# Gadget-Box-atmega32u4.net
KiCad netlist of a schematic drawn in EAGLE
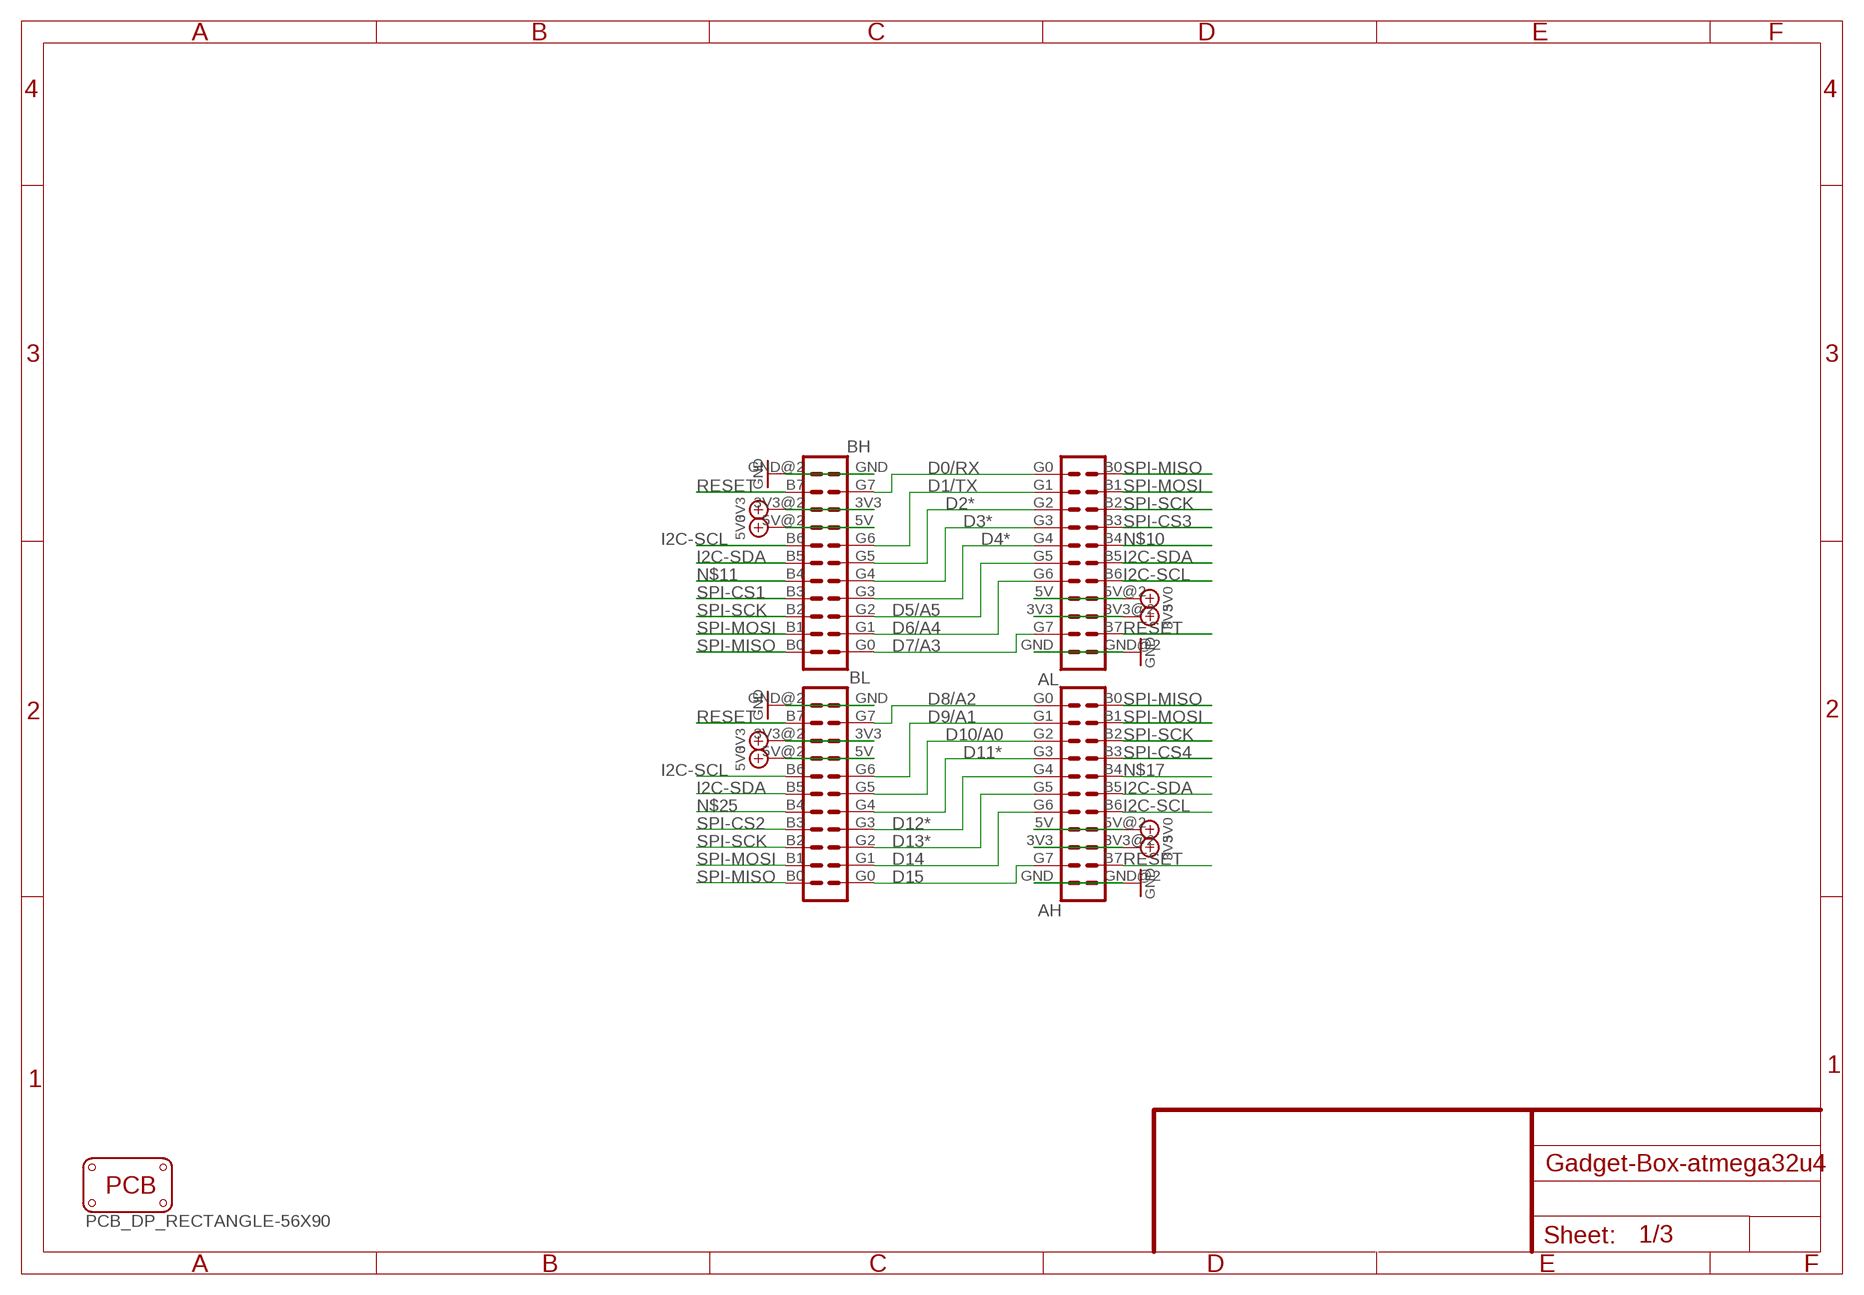
[diagram p0: schematic, sheet 1]
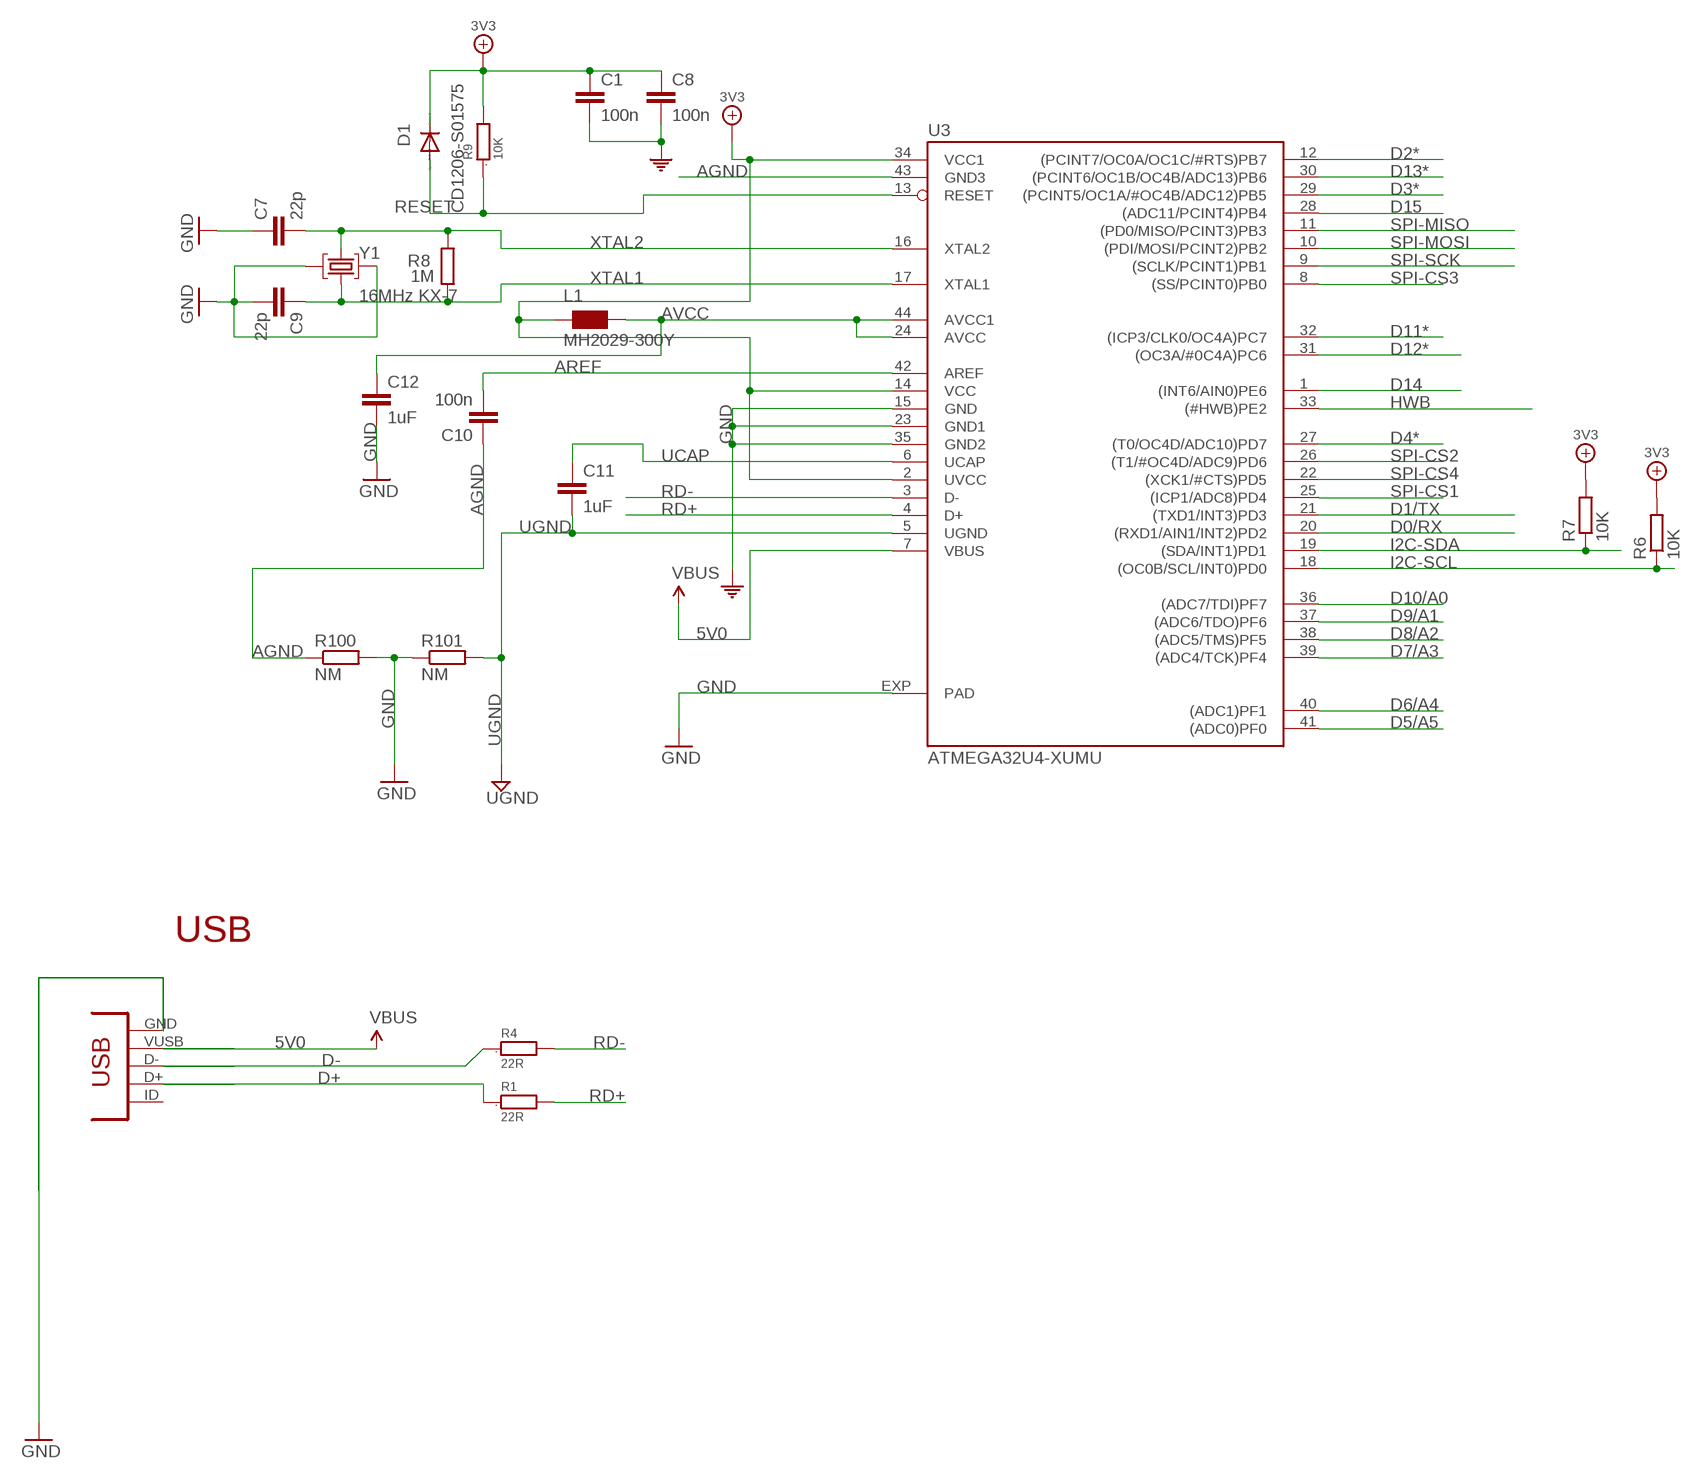
[diagram p1: schematic, sheet 2, part 1 of 2]
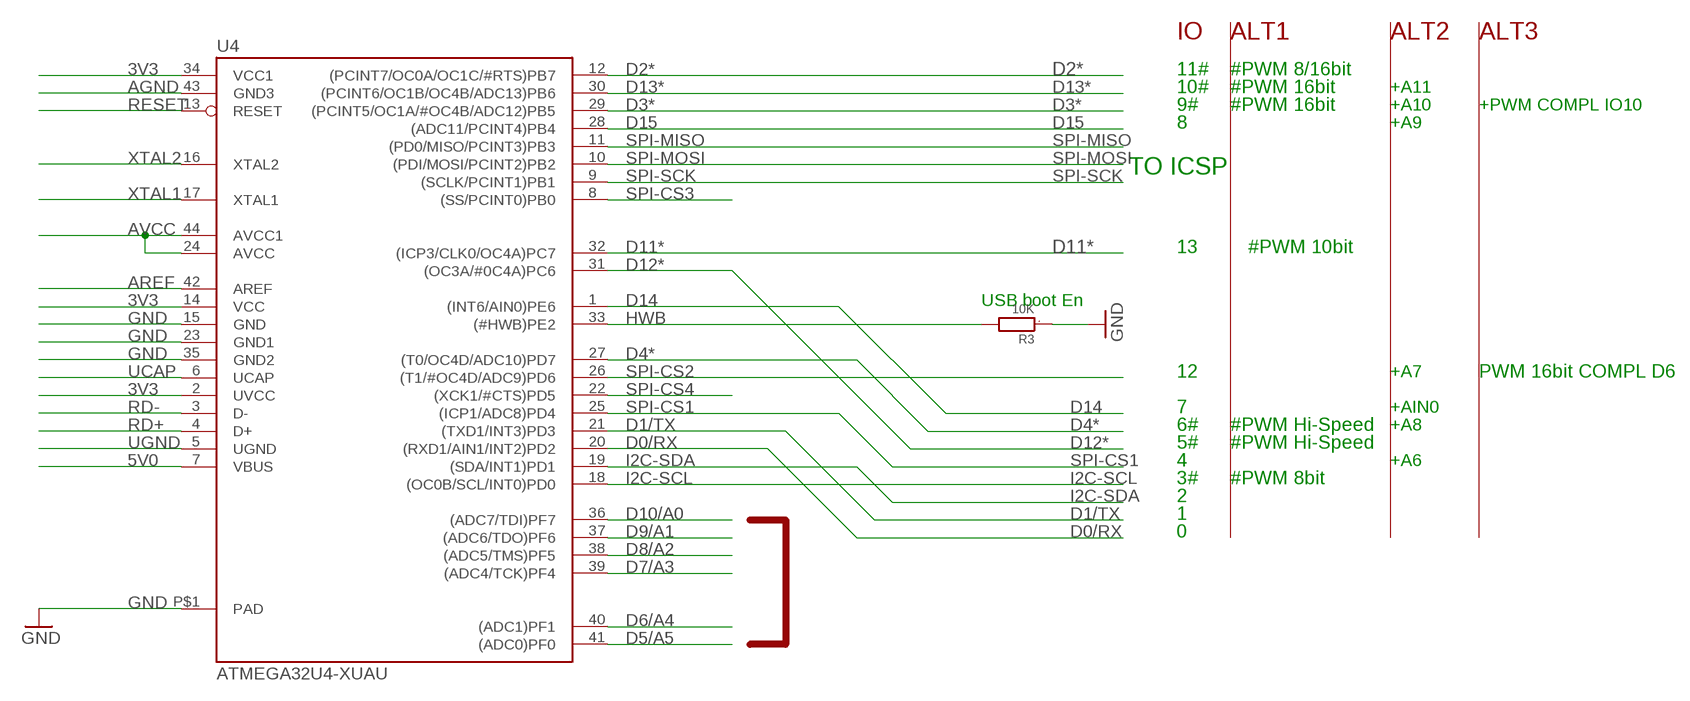
[diagram p2: schematic, sheet 2, part 2 of 2]
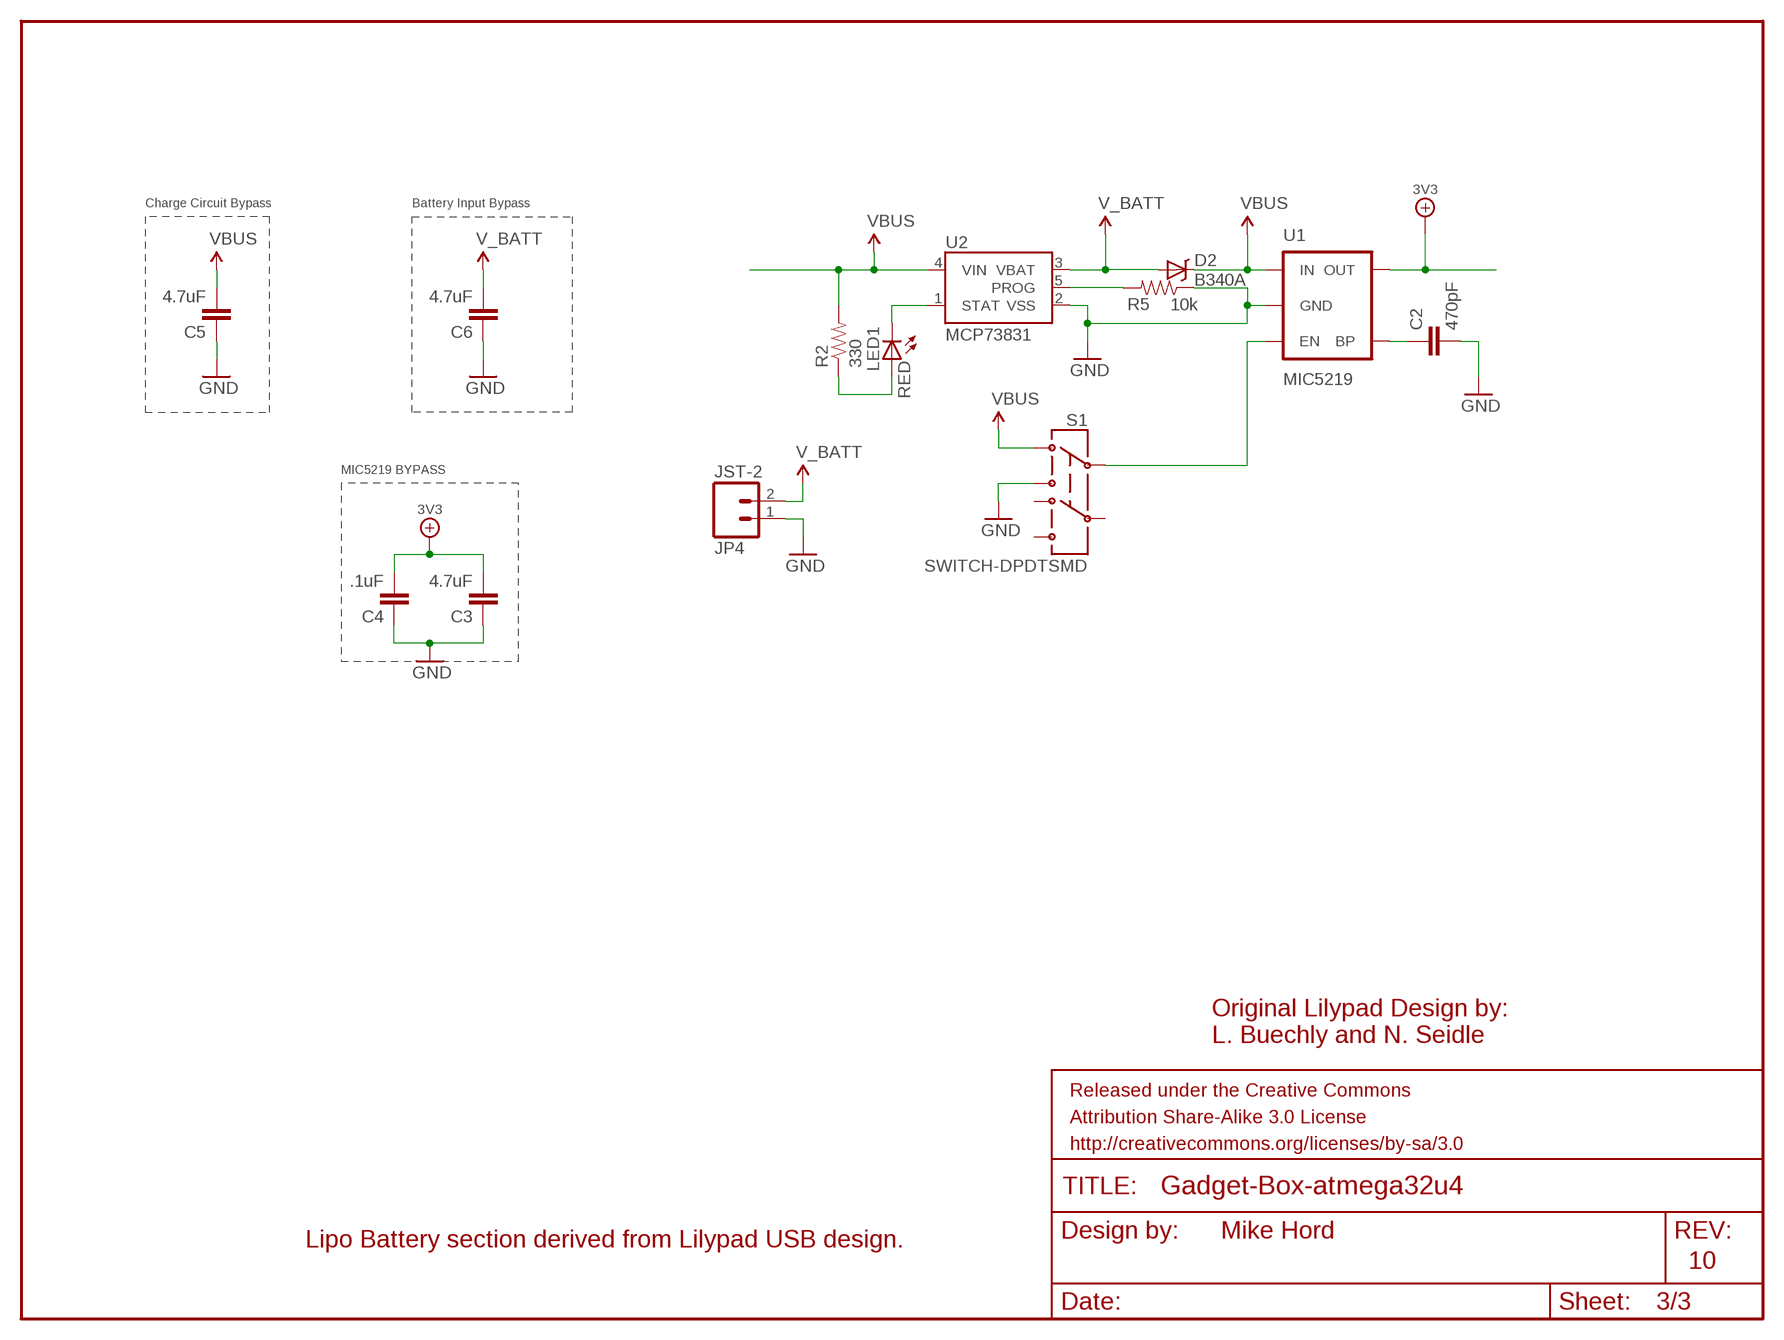
[diagram p3: schematic, sheet 3]

(export (version "E")
  (design (tool "Eeschema 10.0.6"))
  (components
    (comp (ref "C1")
      (value "100n")
      (footprint "eagle-import:C0603-ROUND")
      (libsource (lib "eagle-import") (part "C-EUC0603"))
    )
    (comp (ref "C7")
      (value "22p")
      (footprint "eagle-import:C0603-ROUND")
      (libsource (lib "eagle-import") (part "C-EUC0603"))
    )
    (comp (ref "C8")
      (value "100n")
      (footprint "eagle-import:C0603-ROUND")
      (libsource (lib "eagle-import") (part "C-EUC0603"))
    )
    (comp (ref "C9")
      (value "22p")
      (footprint "eagle-import:C0603-ROUND")
      (libsource (lib "eagle-import") (part "C-EUC0603"))
    )
    (comp (ref "C10")
      (value "100n")
      (footprint "eagle-import:C0603-ROUND")
      (libsource (lib "eagle-import") (part "C-EUC0603"))
    )
    (comp (ref "C11")
      (value "1uF")
      (footprint "eagle-import:C0603-ROUND")
      (libsource (lib "eagle-import") (part "C-EUC0603"))
    )
    (comp (ref "C12")
      (value "1uF")
      (footprint "eagle-import:C0603-ROUND")
      (libsource (lib "eagle-import") (part "C-EUC0603"))
    )
    (comp (ref "D1")
      (value "CD1206-S01575")
      (footprint "eagle-import:MINIMELF")
      (libsource (lib "eagle-import") (part "DIODE-MINIMELF"))
    )
    (comp (ref "L1")
      (value "MH2029-300Y")
      (footprint "eagle-import:0805")
      (libsource (lib "eagle-import") (part "WE-CBF_0805"))
    )
    (comp (ref "R1")
      (value "22R")
      (footprint "eagle-import:0805")
      (libsource (lib "eagle-import") (part "R0805"))
    )
    (comp (ref "R3")
      (value "10K")
      (footprint "eagle-import:0805")
      (libsource (lib "eagle-import") (part "R0805"))
    )
    (comp (ref "R4")
      (value "22R")
      (footprint "eagle-import:0805")
      (libsource (lib "eagle-import") (part "R0805"))
    )
    (comp (ref "R6")
      (value "10K")
      (footprint "eagle-import:R0402")
      (libsource (lib "eagle-import") (part "R-EU_R0402"))
    )
    (comp (ref "R7")
      (value "10K")
      (footprint "eagle-import:R0402")
      (libsource (lib "eagle-import") (part "R-EU_R0402"))
    )
    (comp (ref "R8")
      (value "1M")
      (footprint "eagle-import:R0603-ROUND")
      (libsource (lib "eagle-import") (part "R-EU_R0603"))
    )
    (comp (ref "R9")
      (value "10K")
      (footprint "eagle-import:0805")
      (libsource (lib "eagle-import") (part "R0805"))
    )
    (comp (ref "R100")
      (value "NM")
      (footprint "eagle-import:R0402")
      (libsource (lib "eagle-import") (part "R-EU_R0402"))
    )
    (comp (ref "R101")
      (value "NM")
      (footprint "eagle-import:R0402")
      (libsource (lib "eagle-import") (part "R-EU_R0402"))
    )
    (comp (ref "U3")
      (value "ATMEGA32U4-XUMU")
      (footprint "eagle-import:QFN44ML7X7")
      (libsource (lib "eagle-import") (part "ATMEGA32U4-XUMU"))
    )
    (comp (ref "U4")
      (value "ATMEGA32U4-XUAU")
      (footprint "eagle-import:TQFP44-PAD")
      (libsource (lib "eagle-import") (part "ATMEGA32U4-XUAU"))
    )
    (comp (ref "USB")
      (value "CONN_USB")
      (footprint "eagle-import:CONN_USB_MINI-B")
      (libsource (lib "eagle-import") (part "CONN_USB"))
    )
    (comp (ref "Y1")
      (value "16MHz KX-7")
      (footprint "eagle-import:CRYSTAL-3.2-2.5")
      (libsource (lib "eagle-import") (part "CRYSTAL-3.2-2.5"))
    )
    (comp (ref "AH")
      (value "ECOGECOG_SLOT")
      (footprint "eagle-import:ECOG")
      (libsource (lib "eagle-import") (part "ECOGECOG_SLOT"))
    )
    (comp (ref "AL")
      (value "ECOGECOG_SLOT")
      (footprint "eagle-import:ECOG")
      (libsource (lib "eagle-import") (part "ECOGECOG_SLOT"))
    )
    (comp (ref "BH")
      (value "ECOGECOG_SLOT")
      (footprint "eagle-import:ECOG")
      (libsource (lib "eagle-import") (part "ECOGECOG_SLOT"))
    )
    (comp (ref "BL")
      (value "ECOGECOG_SLOT")
      (footprint "eagle-import:ECOG")
      (libsource (lib "eagle-import") (part "ECOGECOG_SLOT"))
    )
    (comp (ref "PCB1")
      (value "PCB_DP_RECTANGLE-56X90")
      (footprint "eagle-import:DP9056_V1")
      (libsource (lib "eagle-import") (part "PCB_DP_RECTANGLE-56X90"))
    )
    (comp (ref "C2")
      (value "470pF")
      (footprint "eagle-import:0603-CAP")
      (libsource (lib "eagle-import") (part "CAP0603-CAP"))
    )
    (comp (ref "C3")
      (value "4.7uF")
      (footprint "eagle-import:0603-CAP")
      (libsource (lib "eagle-import") (part "CAP0603-CAP"))
    )
    (comp (ref "C4")
      (value ".1uF")
      (footprint "eagle-import:0603-CAP")
      (libsource (lib "eagle-import") (part "CAP0603-CAP"))
    )
    (comp (ref "C5")
      (value "4.7uF")
      (footprint "eagle-import:1206")
      (libsource (lib "eagle-import") (part "CAP1206"))
    )
    (comp (ref "C6")
      (value "4.7uF")
      (footprint "eagle-import:1206")
      (libsource (lib "eagle-import") (part "CAP1206"))
    )
    (comp (ref "D2")
      (value "B340A")
      (footprint "eagle-import:SMA-DIODE")
      (libsource (lib "eagle-import") (part "DIODE-SCHOTTKY_"))
    )
    (comp (ref "JP4")
      (value "JST-2")
      (footprint "eagle-import:JST-2-SMD")
      (libsource (lib "eagle-import") (part "M02-JST-2MM-SMT"))
    )
    (comp (ref "LED1")
      (value "RED")
      (footprint "eagle-import:LED-0603")
      (libsource (lib "eagle-import") (part "LED0603"))
    )
    (comp (ref "R2")
      (value "330")
      (footprint "eagle-import:0603-RES")
      (libsource (lib "eagle-import") (part "RESISTOR0603-RES"))
    )
    (comp (ref "R5")
      (value "10k")
      (footprint "eagle-import:0603-RES")
      (libsource (lib "eagle-import") (part "RESISTOR0603-RES"))
    )
    (comp (ref "S1")
      (value "SWITCH-DPDTSMD")
      (footprint "eagle-import:AYZ0202")
      (libsource (lib "eagle-import") (part "SWITCH-DPDTSMD"))
    )
    (comp (ref "U1")
      (value "MIC5219")
      (footprint "eagle-import:SOT23-5")
      (libsource (lib "eagle-import") (part "V_REG_MIC5219SMD"))
    )
    (comp (ref "U2")
      (value "MCP73831")
      (footprint "eagle-import:SOT23-5")
      (libsource (lib "eagle-import") (part "MCP73831"))
    )
  )
  (nets
    (net (code "1") (name "3V3") (class "Default")
      (node (ref "AH") (pin "3V3") (pinfunction "3V3_3V3") (pintype "passive"))
      (node (ref "AH") (pin "3V3@2") (pinfunction "3V3_3V3@2") (pintype "passive"))
      (node (ref "AL") (pin "3V3") (pinfunction "3V3_3V3") (pintype "passive"))
      (node (ref "AL") (pin "3V3@2") (pinfunction "3V3_3V3@2") (pintype "passive"))
      (node (ref "BH") (pin "3V3") (pinfunction "3V3_3V3") (pintype "passive"))
      (node (ref "BH") (pin "3V3@2") (pinfunction "3V3_3V3@2") (pintype "passive"))
      (node (ref "BL") (pin "3V3") (pinfunction "3V3_3V3") (pintype "passive"))
      (node (ref "BL") (pin "3V3@2") (pinfunction "3V3_3V3@2") (pintype "passive"))
      (node (ref "C1") (pin "1") (pinfunction "1_1") (pintype "passive"))
      (node (ref "C3") (pin "2") (pinfunction "2_2") (pintype "passive"))
      (node (ref "C4") (pin "2") (pinfunction "2_2") (pintype "passive"))
      (node (ref "C8") (pin "1") (pinfunction "1_1") (pintype "passive"))
      (node (ref "D1") (pin "C") (pinfunction "C_C") (pintype "passive"))
      (node (ref "L1") (pin "1") (pinfunction "1_1") (pintype "passive"))
      (node (ref "R6") (pin "2") (pinfunction "2_2") (pintype "passive"))
      (node (ref "R7") (pin "2") (pinfunction "2_2") (pintype "passive"))
      (node (ref "R9") (pin "2") (pinfunction "2_2") (pintype "passive"))
      (node (ref "U1") (pin "5") (pinfunction "OUT_5") (pintype "passive"))
      (node (ref "U3") (pin "14") (pinfunction "VCC_14") (pintype "power_in"))
      (node (ref "U3") (pin "2") (pinfunction "UVCC_2") (pintype "power_in"))
      (node (ref "U3") (pin "34") (pinfunction "VCC1_34") (pintype "power_in"))
      (node (ref "U4") (pin "14") (pinfunction "VCC_14") (pintype "power_in"))
      (node (ref "U4") (pin "2") (pinfunction "UVCC_2") (pintype "power_in"))
      (node (ref "U4") (pin "34") (pinfunction "VCC1_34") (pintype "power_in"))
    )
    (net (code "2") (name "5V0") (class "Default")
      (node (ref "AH") (pin "5V") (pinfunction "5V_5V") (pintype "passive"))
      (node (ref "AH") (pin "5V@2") (pinfunction "5V_5V@2") (pintype "passive"))
      (node (ref "AL") (pin "5V") (pinfunction "5V_5V") (pintype "passive"))
      (node (ref "AL") (pin "5V@2") (pinfunction "5V_5V@2") (pintype "passive"))
      (node (ref "BH") (pin "5V") (pinfunction "5V_5V") (pintype "passive"))
      (node (ref "BH") (pin "5V@2") (pinfunction "5V_5V@2") (pintype "passive"))
      (node (ref "BL") (pin "5V") (pinfunction "5V_5V") (pintype "passive"))
      (node (ref "BL") (pin "5V@2") (pinfunction "5V_5V@2") (pintype "passive"))
      (node (ref "C5") (pin "2") (pinfunction "2_2") (pintype "passive"))
      (node (ref "D2") (pin "C") (pinfunction "C_C") (pintype "passive"))
      (node (ref "R2") (pin "2") (pinfunction "2_2") (pintype "passive"))
      (node (ref "S1") (pin "1") (pinfunction "1_1") (pintype "bidirectional"))
      (node (ref "U1") (pin "1") (pinfunction "IN_1") (pintype "input"))
      (node (ref "U2") (pin "4") (pinfunction "VIN_4") (pintype "power_in"))
      (node (ref "U3") (pin "7") (pinfunction "VBUS_7") (pintype "input"))
      (node (ref "U4") (pin "7") (pinfunction "VBUS_7") (pintype "input"))
      (node (ref "USB") (pin "VUSB") (pinfunction "VUSB_VUSB") (pintype "bidirectional"))
    )
    (net (code "3") (name "AGND") (class "Default")
      (node (ref "C10") (pin "1") (pinfunction "1_1") (pintype "passive"))
      (node (ref "R100") (pin "1") (pinfunction "1_1") (pintype "passive"))
      (node (ref "U3") (pin "43") (pinfunction "GND3_43") (pintype "power_in"))
      (node (ref "U4") (pin "43") (pinfunction "GND3_43") (pintype "power_in"))
    )
    (net (code "4") (name "AREF") (class "Default")
      (node (ref "C10") (pin "2") (pinfunction "2_2") (pintype "passive"))
      (node (ref "U3") (pin "42") (pinfunction "AREF_42") (pintype "power_in"))
      (node (ref "U4") (pin "42") (pinfunction "AREF_42") (pintype "power_in"))
    )
    (net (code "5") (name "AVCC") (class "Default")
      (node (ref "C12") (pin "1") (pinfunction "1_1") (pintype "passive"))
      (node (ref "L1") (pin "2") (pinfunction "2_2") (pintype "passive"))
      (node (ref "U3") (pin "24") (pinfunction "AVCC_24") (pintype "power_in"))
      (node (ref "U3") (pin "44") (pinfunction "AVCC1_44") (pintype "power_in"))
      (node (ref "U4") (pin "24") (pinfunction "AVCC_24") (pintype "power_in"))
      (node (ref "U4") (pin "44") (pinfunction "AVCC1_44") (pintype "power_in"))
    )
    (net (code "6") (name "D+") (class "Default")
      (node (ref "R1") (pin "1") (pinfunction "1_1") (pintype "passive"))
      (node (ref "USB") (pin "D+") (pinfunction "D+_D+") (pintype "bidirectional"))
    )
    (net (code "7") (name "D-") (class "Default")
      (node (ref "R4") (pin "1") (pinfunction "1_1") (pintype "passive"))
      (node (ref "USB") (pin "D-") (pinfunction "D-_D-") (pintype "bidirectional"))
    )
    (net (code "8") (name "D0{slash}RX") (class "Default")
      (node (ref "AL") (pin "G0") (pinfunction "G0_G0") (pintype "passive"))
      (node (ref "BH") (pin "G7") (pinfunction "G7_G7") (pintype "passive"))
      (node (ref "U3") (pin "20") (pinfunction "(RXD1/AIN1/INT2)PD2_20") (pintype "bidirectional"))
      (node (ref "U4") (pin "20") (pinfunction "(RXD1/AIN1/INT2)PD2_20") (pintype "bidirectional"))
    )
    (net (code "9") (name "D1{slash}TX") (class "Default")
      (node (ref "AL") (pin "G1") (pinfunction "G1_G1") (pintype "passive"))
      (node (ref "BH") (pin "G6") (pinfunction "G6_G6") (pintype "passive"))
      (node (ref "U3") (pin "21") (pinfunction "(TXD1/INT3)PD3_21") (pintype "bidirectional"))
      (node (ref "U4") (pin "21") (pinfunction "(TXD1/INT3)PD3_21") (pintype "bidirectional"))
    )
    (net (code "10") (name "D2*") (class "Default")
      (node (ref "AL") (pin "G2") (pinfunction "G2_G2") (pintype "passive"))
      (node (ref "BH") (pin "G5") (pinfunction "G5_G5") (pintype "passive"))
      (node (ref "U3") (pin "12") (pinfunction "(PCINT7/OC0A/OC1C/#RTS)PB7_12") (pintype "bidirectional"))
      (node (ref "U4") (pin "12") (pinfunction "(PCINT7/OC0A/OC1C/#RTS)PB7_12") (pintype "bidirectional"))
    )
    (net (code "11") (name "D3*") (class "Default")
      (node (ref "AL") (pin "G3") (pinfunction "G3_G3") (pintype "passive"))
      (node (ref "BH") (pin "G4") (pinfunction "G4_G4") (pintype "passive"))
      (node (ref "U3") (pin "29") (pinfunction "(PCINT5/OC1A/#OC4B/ADC12)PB5_29") (pintype "bidirectional"))
      (node (ref "U4") (pin "29") (pinfunction "(PCINT5/OC1A/#OC4B/ADC12)PB5_29") (pintype "bidirectional"))
    )
    (net (code "12") (name "D4*") (class "Default")
      (node (ref "AL") (pin "G4") (pinfunction "G4_G4") (pintype "passive"))
      (node (ref "BH") (pin "G3") (pinfunction "G3_G3") (pintype "passive"))
      (node (ref "U3") (pin "27") (pinfunction "(T0/OC4D/ADC10)PD7_27") (pintype "bidirectional"))
      (node (ref "U4") (pin "27") (pinfunction "(T0/OC4D/ADC10)PD7_27") (pintype "bidirectional"))
    )
    (net (code "13") (name "D5{slash}A5") (class "Default")
      (node (ref "AL") (pin "G5") (pinfunction "G5_G5") (pintype "passive"))
      (node (ref "BH") (pin "G2") (pinfunction "G2_G2") (pintype "passive"))
      (node (ref "U3") (pin "41") (pinfunction "(ADC0)PF0_41") (pintype "bidirectional"))
      (node (ref "U4") (pin "41") (pinfunction "(ADC0)PF0_41") (pintype "bidirectional"))
    )
    (net (code "14") (name "D6{slash}A4") (class "Default")
      (node (ref "AL") (pin "G6") (pinfunction "G6_G6") (pintype "passive"))
      (node (ref "BH") (pin "G1") (pinfunction "G1_G1") (pintype "passive"))
      (node (ref "U3") (pin "40") (pinfunction "(ADC1)PF1_40") (pintype "bidirectional"))
      (node (ref "U4") (pin "40") (pinfunction "(ADC1)PF1_40") (pintype "bidirectional"))
    )
    (net (code "15") (name "D7{slash}A3") (class "Default")
      (node (ref "AL") (pin "G7") (pinfunction "G7_G7") (pintype "passive"))
      (node (ref "BH") (pin "G0") (pinfunction "G0_G0") (pintype "passive"))
      (node (ref "U3") (pin "39") (pinfunction "(ADC4/TCK)PF4_39") (pintype "bidirectional"))
      (node (ref "U4") (pin "39") (pinfunction "(ADC4/TCK)PF4_39") (pintype "bidirectional"))
    )
    (net (code "16") (name "D8{slash}A2") (class "Default")
      (node (ref "AH") (pin "G0") (pinfunction "G0_G0") (pintype "passive"))
      (node (ref "BL") (pin "G7") (pinfunction "G7_G7") (pintype "passive"))
      (node (ref "U3") (pin "38") (pinfunction "(ADC5/TMS)PF5_38") (pintype "bidirectional"))
      (node (ref "U4") (pin "38") (pinfunction "(ADC5/TMS)PF5_38") (pintype "bidirectional"))
    )
    (net (code "17") (name "D9{slash}A1") (class "Default")
      (node (ref "AH") (pin "G1") (pinfunction "G1_G1") (pintype "passive"))
      (node (ref "BL") (pin "G6") (pinfunction "G6_G6") (pintype "passive"))
      (node (ref "U3") (pin "37") (pinfunction "(ADC6/TDO)PF6_37") (pintype "bidirectional"))
      (node (ref "U4") (pin "37") (pinfunction "(ADC6/TDO)PF6_37") (pintype "bidirectional"))
    )
    (net (code "18") (name "D10{slash}A0") (class "Default")
      (node (ref "AH") (pin "G2") (pinfunction "G2_G2") (pintype "passive"))
      (node (ref "BL") (pin "G5") (pinfunction "G5_G5") (pintype "passive"))
      (node (ref "U3") (pin "36") (pinfunction "(ADC7/TDI)PF7_36") (pintype "bidirectional"))
      (node (ref "U4") (pin "36") (pinfunction "(ADC7/TDI)PF7_36") (pintype "bidirectional"))
    )
    (net (code "19") (name "D11*") (class "Default")
      (node (ref "AH") (pin "G3") (pinfunction "G3_G3") (pintype "passive"))
      (node (ref "BL") (pin "G4") (pinfunction "G4_G4") (pintype "passive"))
      (node (ref "U3") (pin "32") (pinfunction "(ICP3/CLK0/OC4A)PC7_32") (pintype "bidirectional"))
      (node (ref "U4") (pin "32") (pinfunction "(ICP3/CLK0/OC4A)PC7_32") (pintype "bidirectional"))
    )
    (net (code "20") (name "D12*") (class "Default")
      (node (ref "AH") (pin "G4") (pinfunction "G4_G4") (pintype "passive"))
      (node (ref "BL") (pin "G3") (pinfunction "G3_G3") (pintype "passive"))
      (node (ref "U3") (pin "31") (pinfunction "(OC3A/#0C4A)PC6_31") (pintype "bidirectional"))
      (node (ref "U4") (pin "31") (pinfunction "(OC3A/#0C4A)PC6_31") (pintype "bidirectional"))
    )
    (net (code "21") (name "D13*") (class "Default")
      (node (ref "AH") (pin "G5") (pinfunction "G5_G5") (pintype "passive"))
      (node (ref "BL") (pin "G2") (pinfunction "G2_G2") (pintype "passive"))
      (node (ref "U3") (pin "30") (pinfunction "(PCINT6/OC1B/OC4B/ADC13)PB6_30") (pintype "bidirectional"))
      (node (ref "U4") (pin "30") (pinfunction "(PCINT6/OC1B/OC4B/ADC13)PB6_30") (pintype "bidirectional"))
    )
    (net (code "22") (name "D14") (class "Default")
      (node (ref "AH") (pin "G6") (pinfunction "G6_G6") (pintype "passive"))
      (node (ref "BL") (pin "G1") (pinfunction "G1_G1") (pintype "passive"))
      (node (ref "U3") (pin "1") (pinfunction "(INT6/AIN0)PE6_1") (pintype "bidirectional"))
      (node (ref "U4") (pin "1") (pinfunction "(INT6/AIN0)PE6_1") (pintype "bidirectional"))
    )
    (net (code "23") (name "D15") (class "Default")
      (node (ref "AH") (pin "G7") (pinfunction "G7_G7") (pintype "passive"))
      (node (ref "BL") (pin "G0") (pinfunction "G0_G0") (pintype "passive"))
      (node (ref "U3") (pin "28") (pinfunction "(ADC11/PCINT4)PB4_28") (pintype "bidirectional"))
      (node (ref "U4") (pin "28") (pinfunction "(ADC11/PCINT4)PB4_28") (pintype "bidirectional"))
    )
    (net (code "24") (name "GND") (class "Default")
      (node (ref "AH") (pin "GND") (pinfunction "GND_GND") (pintype "passive"))
      (node (ref "AH") (pin "GND@2") (pinfunction "GND_GND@2") (pintype "passive"))
      (node (ref "AL") (pin "GND") (pinfunction "GND_GND") (pintype "passive"))
      (node (ref "AL") (pin "GND@2") (pinfunction "GND_GND@2") (pintype "passive"))
      (node (ref "BH") (pin "GND") (pinfunction "GND_GND") (pintype "passive"))
      (node (ref "BH") (pin "GND@2") (pinfunction "GND_GND@2") (pintype "passive"))
      (node (ref "BL") (pin "GND") (pinfunction "GND_GND") (pintype "passive"))
      (node (ref "BL") (pin "GND@2") (pinfunction "GND_GND@2") (pintype "passive"))
      (node (ref "C1") (pin "2") (pinfunction "2_2") (pintype "passive"))
      (node (ref "C12") (pin "2") (pinfunction "2_2") (pintype "passive"))
      (node (ref "C2") (pin "2") (pinfunction "2_2") (pintype "passive"))
      (node (ref "C3") (pin "1") (pinfunction "1_1") (pintype "passive"))
      (node (ref "C4") (pin "1") (pinfunction "1_1") (pintype "passive"))
      (node (ref "C5") (pin "1") (pinfunction "1_1") (pintype "passive"))
      (node (ref "C6") (pin "1") (pinfunction "1_1") (pintype "passive"))
      (node (ref "C7") (pin "1") (pinfunction "1_1") (pintype "passive"))
      (node (ref "C8") (pin "2") (pinfunction "2_2") (pintype "passive"))
      (node (ref "C9") (pin "2") (pinfunction "2_2") (pintype "passive"))
      (node (ref "JP4") (pin "1") (pinfunction "2_1") (pintype "passive"))
      (node (ref "R100") (pin "2") (pinfunction "2_2") (pintype "passive"))
      (node (ref "R101") (pin "1") (pinfunction "1_1") (pintype "passive"))
      (node (ref "R3") (pin "1") (pinfunction "1_1") (pintype "passive"))
      (node (ref "R5") (pin "1") (pinfunction "1_1") (pintype "passive"))
      (node (ref "S1") (pin "3") (pinfunction "3_3") (pintype "bidirectional"))
      (node (ref "U1") (pin "2") (pinfunction "GND_2") (pintype "input"))
      (node (ref "U2") (pin "2") (pinfunction "VSS_2") (pintype "power_in"))
      (node (ref "U3") (pin "15") (pinfunction "GND_15") (pintype "power_in"))
      (node (ref "U3") (pin "23") (pinfunction "GND1_23") (pintype "power_in"))
      (node (ref "U3") (pin "35") (pinfunction "GND2_35") (pintype "power_in"))
      (node (ref "U3") (pin "EXP") (pinfunction "PAD_EXP") (pintype "power_in"))
      (node (ref "U4") (pin "15") (pinfunction "GND_15") (pintype "power_in"))
      (node (ref "U4") (pin "23") (pinfunction "GND1_23") (pintype "power_in"))
      (node (ref "U4") (pin "35") (pinfunction "GND2_35") (pintype "power_in"))
      (node (ref "U4") (pin "P$1") (pinfunction "PAD_P$1") (pintype "power_in"))
      (node (ref "USB") (pin "GND") (pinfunction "GND_GND") (pintype "bidirectional"))
      (node (ref "Y1") (pin "2") (pinfunction "GND_2") (pintype "passive"))
      (node (ref "Y1") (pin "4") (pinfunction "GND_4") (pintype "passive"))
    )
    (net (code "25") (name "HWB") (class "Default")
      (node (ref "R3") (pin "2") (pinfunction "2_2") (pintype "passive"))
      (node (ref "U3") (pin "33") (pinfunction "(#HWB)PE2_33") (pintype "bidirectional"))
      (node (ref "U4") (pin "33") (pinfunction "(#HWB)PE2_33") (pintype "bidirectional"))
    )
    (net (code "26") (name "I2C-SCL") (class "Default")
      (node (ref "AH") (pin "B6") (pinfunction "B6_B6") (pintype "passive"))
      (node (ref "AL") (pin "B6") (pinfunction "B6_B6") (pintype "passive"))
      (node (ref "BH") (pin "B6") (pinfunction "B6_B6") (pintype "passive"))
      (node (ref "BL") (pin "B6") (pinfunction "B6_B6") (pintype "passive"))
      (node (ref "R6") (pin "1") (pinfunction "1_1") (pintype "passive"))
      (node (ref "U3") (pin "18") (pinfunction "(OC0B/SCL/INT0)PD0_18") (pintype "bidirectional"))
      (node (ref "U4") (pin "18") (pinfunction "(OC0B/SCL/INT0)PD0_18") (pintype "bidirectional"))
    )
    (net (code "27") (name "I2C-SDA") (class "Default")
      (node (ref "AH") (pin "B5") (pinfunction "B5_B5") (pintype "passive"))
      (node (ref "AL") (pin "B5") (pinfunction "B5_B5") (pintype "passive"))
      (node (ref "BH") (pin "B5") (pinfunction "B5_B5") (pintype "passive"))
      (node (ref "BL") (pin "B5") (pinfunction "B5_B5") (pintype "passive"))
      (node (ref "R7") (pin "1") (pinfunction "1_1") (pintype "passive"))
      (node (ref "U3") (pin "19") (pinfunction "(SDA/INT1)PD1_19") (pintype "bidirectional"))
      (node (ref "U4") (pin "19") (pinfunction "(SDA/INT1)PD1_19") (pintype "bidirectional"))
    )
    (net (code "28") (name "N$10") (class "Default")
      (node (ref "AL") (pin "B4") (pinfunction "B4_B4") (pintype "passive"))
    )
    (net (code "29") (name "N$11") (class "Default")
      (node (ref "BH") (pin "B4") (pinfunction "B4_B4") (pintype "passive"))
    )
    (net (code "30") (name "N$17") (class "Default")
      (node (ref "AH") (pin "B4") (pinfunction "B4_B4") (pintype "passive"))
    )
    (net (code "31") (name "N$25") (class "Default")
      (node (ref "BL") (pin "B4") (pinfunction "B4_B4") (pintype "passive"))
    )
    (net (code "32") (name "Net-(LED1-PadA)") (class "Default")
      (node (ref "LED1") (pin "A") (pinfunction "A_A") (pintype "passive"))
      (node (ref "R2") (pin "1") (pinfunction "1_1") (pintype "passive"))
    )
    (net (code "33") (name "Net-(U1-BP)") (class "Default")
      (node (ref "C2") (pin "1") (pinfunction "1_1") (pintype "passive"))
      (node (ref "U1") (pin "4") (pinfunction "BP_4") (pintype "input"))
    )
    (net (code "34") (name "Net-(U1-EN)") (class "Default")
      (node (ref "S1") (pin "2") (pinfunction "2_2") (pintype "bidirectional"))
      (node (ref "U1") (pin "3") (pinfunction "EN_3") (pintype "input"))
    )
    (net (code "35") (name "Net-(U2-PROG)") (class "Default")
      (node (ref "R5") (pin "2") (pinfunction "2_2") (pintype "passive"))
      (node (ref "U2") (pin "5") (pinfunction "PROG_5") (pintype "input"))
    )
    (net (code "36") (name "Net-(U2-STAT)") (class "Default")
      (node (ref "LED1") (pin "C") (pinfunction "C_C") (pintype "passive"))
      (node (ref "U2") (pin "1") (pinfunction "STAT_1") (pintype "output"))
    )
    (net (code "37") (name "RD+") (class "Default")
      (node (ref "R1") (pin "2") (pinfunction "2_2") (pintype "passive"))
      (node (ref "U3") (pin "4") (pinfunction "D+_4") (pintype "bidirectional"))
      (node (ref "U4") (pin "4") (pinfunction "D+_4") (pintype "bidirectional"))
    )
    (net (code "38") (name "RD-") (class "Default")
      (node (ref "R4") (pin "2") (pinfunction "2_2") (pintype "passive"))
      (node (ref "U3") (pin "3") (pinfunction "D-_3") (pintype "bidirectional"))
      (node (ref "U4") (pin "3") (pinfunction "D-_3") (pintype "bidirectional"))
    )
    (net (code "39") (name "RESET") (class "Default")
      (node (ref "AH") (pin "B7") (pinfunction "B7_B7") (pintype "passive"))
      (node (ref "AL") (pin "B7") (pinfunction "B7_B7") (pintype "passive"))
      (node (ref "BH") (pin "B7") (pinfunction "B7_B7") (pintype "passive"))
      (node (ref "BL") (pin "B7") (pinfunction "B7_B7") (pintype "passive"))
      (node (ref "D1") (pin "A") (pinfunction "A_A") (pintype "passive"))
      (node (ref "R9") (pin "1") (pinfunction "1_1") (pintype "passive"))
      (node (ref "U3") (pin "13") (pinfunction "RESET_13") (pintype "input"))
      (node (ref "U4") (pin "13") (pinfunction "RESET_13") (pintype "input"))
    )
    (net (code "40") (name "SPI-CS1") (class "Default")
      (node (ref "BH") (pin "B3") (pinfunction "B3_B3") (pintype "passive"))
      (node (ref "U3") (pin "25") (pinfunction "(ICP1/ADC8)PD4_25") (pintype "bidirectional"))
      (node (ref "U4") (pin "25") (pinfunction "(ICP1/ADC8)PD4_25") (pintype "bidirectional"))
    )
    (net (code "41") (name "SPI-CS2") (class "Default")
      (node (ref "BL") (pin "B3") (pinfunction "B3_B3") (pintype "passive"))
      (node (ref "U3") (pin "26") (pinfunction "(T1/#OC4D/ADC9)PD6_26") (pintype "bidirectional"))
      (node (ref "U4") (pin "26") (pinfunction "(T1/#OC4D/ADC9)PD6_26") (pintype "bidirectional"))
    )
    (net (code "42") (name "SPI-CS3") (class "Default")
      (node (ref "AL") (pin "B3") (pinfunction "B3_B3") (pintype "passive"))
      (node (ref "U3") (pin "8") (pinfunction "(SS/PCINT0)PB0_8") (pintype "bidirectional"))
      (node (ref "U4") (pin "8") (pinfunction "(SS/PCINT0)PB0_8") (pintype "bidirectional"))
    )
    (net (code "43") (name "SPI-CS4") (class "Default")
      (node (ref "AH") (pin "B3") (pinfunction "B3_B3") (pintype "passive"))
      (node (ref "U3") (pin "22") (pinfunction "(XCK1/#CTS)PD5_22") (pintype "bidirectional"))
      (node (ref "U4") (pin "22") (pinfunction "(XCK1/#CTS)PD5_22") (pintype "bidirectional"))
    )
    (net (code "44") (name "SPI-MISO") (class "Default")
      (node (ref "AH") (pin "B0") (pinfunction "B0_B0") (pintype "passive"))
      (node (ref "AL") (pin "B0") (pinfunction "B0_B0") (pintype "passive"))
      (node (ref "BH") (pin "B0") (pinfunction "B0_B0") (pintype "passive"))
      (node (ref "BL") (pin "B0") (pinfunction "B0_B0") (pintype "passive"))
      (node (ref "U3") (pin "11") (pinfunction "(PD0/MISO/PCINT3)PB3_11") (pintype "bidirectional"))
      (node (ref "U4") (pin "11") (pinfunction "(PD0/MISO/PCINT3)PB3_11") (pintype "bidirectional"))
    )
    (net (code "45") (name "SPI-MOSI") (class "Default")
      (node (ref "AH") (pin "B1") (pinfunction "B1_B1") (pintype "passive"))
      (node (ref "AL") (pin "B1") (pinfunction "B1_B1") (pintype "passive"))
      (node (ref "BH") (pin "B1") (pinfunction "B1_B1") (pintype "passive"))
      (node (ref "BL") (pin "B1") (pinfunction "B1_B1") (pintype "passive"))
      (node (ref "U3") (pin "10") (pinfunction "(PDI/MOSI/PCINT2)PB2_10") (pintype "bidirectional"))
      (node (ref "U4") (pin "10") (pinfunction "(PDI/MOSI/PCINT2)PB2_10") (pintype "bidirectional"))
    )
    (net (code "46") (name "SPI-SCK") (class "Default")
      (node (ref "AH") (pin "B2") (pinfunction "B2_B2") (pintype "passive"))
      (node (ref "AL") (pin "B2") (pinfunction "B2_B2") (pintype "passive"))
      (node (ref "BH") (pin "B2") (pinfunction "B2_B2") (pintype "passive"))
      (node (ref "BL") (pin "B2") (pinfunction "B2_B2") (pintype "passive"))
      (node (ref "U3") (pin "9") (pinfunction "(SCLK/PCINT1)PB1_9") (pintype "bidirectional"))
      (node (ref "U4") (pin "9") (pinfunction "(SCLK/PCINT1)PB1_9") (pintype "bidirectional"))
    )
    (net (code "47") (name "UCAP") (class "Default")
      (node (ref "C11") (pin "1") (pinfunction "1_1") (pintype "passive"))
      (node (ref "U3") (pin "6") (pinfunction "UCAP_6") (pintype "passive"))
      (node (ref "U4") (pin "6") (pinfunction "UCAP_6") (pintype "passive"))
    )
    (net (code "48") (name "UGND") (class "Default")
      (node (ref "C11") (pin "2") (pinfunction "2_2") (pintype "passive"))
      (node (ref "R101") (pin "2") (pinfunction "2_2") (pintype "passive"))
      (node (ref "U3") (pin "5") (pinfunction "UGND_5") (pintype "power_in"))
      (node (ref "U4") (pin "5") (pinfunction "UGND_5") (pintype "power_in"))
    )
    (net (code "49") (name "V_BATT") (class "Default")
      (node (ref "C6") (pin "2") (pinfunction "2_2") (pintype "passive"))
      (node (ref "D2") (pin "A") (pinfunction "A_A") (pintype "passive"))
      (node (ref "JP4") (pin "2") (pinfunction "1_2") (pintype "passive"))
      (node (ref "U2") (pin "3") (pinfunction "VBAT_3") (pintype "power_in"))
    )
    (net (code "50") (name "XTAL1") (class "Default")
      (node (ref "C9") (pin "1") (pinfunction "1_1") (pintype "passive"))
      (node (ref "R8") (pin "1") (pinfunction "1_1") (pintype "passive"))
      (node (ref "U3") (pin "17") (pinfunction "XTAL1_17") (pintype "bidirectional"))
      (node (ref "U4") (pin "17") (pinfunction "XTAL1_17") (pintype "bidirectional"))
      (node (ref "Y1") (pin "1") (pinfunction "C1_1") (pintype "passive"))
    )
    (net (code "51") (name "XTAL2") (class "Default")
      (node (ref "C7") (pin "2") (pinfunction "2_2") (pintype "passive"))
      (node (ref "R8") (pin "2") (pinfunction "2_2") (pintype "passive"))
      (node (ref "U3") (pin "16") (pinfunction "XTAL2_16") (pintype "bidirectional"))
      (node (ref "U4") (pin "16") (pinfunction "XTAL2_16") (pintype "bidirectional"))
      (node (ref "Y1") (pin "3") (pinfunction "C2_3") (pintype "passive"))
    )
    (net (code "52") (name "unconnected-(S1-Pad4)") (class "Default")
      (node (ref "S1") (pin "4") (pinfunction "4_4") (pintype "bidirectional"))
    )
    (net (code "53") (name "unconnected-(S1-Pad5)") (class "Default")
      (node (ref "S1") (pin "5") (pinfunction "5_5") (pintype "bidirectional"))
    )
    (net (code "54") (name "unconnected-(S1-Pad6)") (class "Default")
      (node (ref "S1") (pin "6") (pinfunction "6_6") (pintype "bidirectional"))
    )
    (net (code "55") (name "unconnected-(USBB-USBID-PadID)") (class "Default")
      (node (ref "USB") (pin "ID") (pinfunction "USBID_ID") (pintype "bidirectional"))
    )
  )
)
